# FPGA_Power.net
KiCad netlist of a schematic drawn in Altium Designer
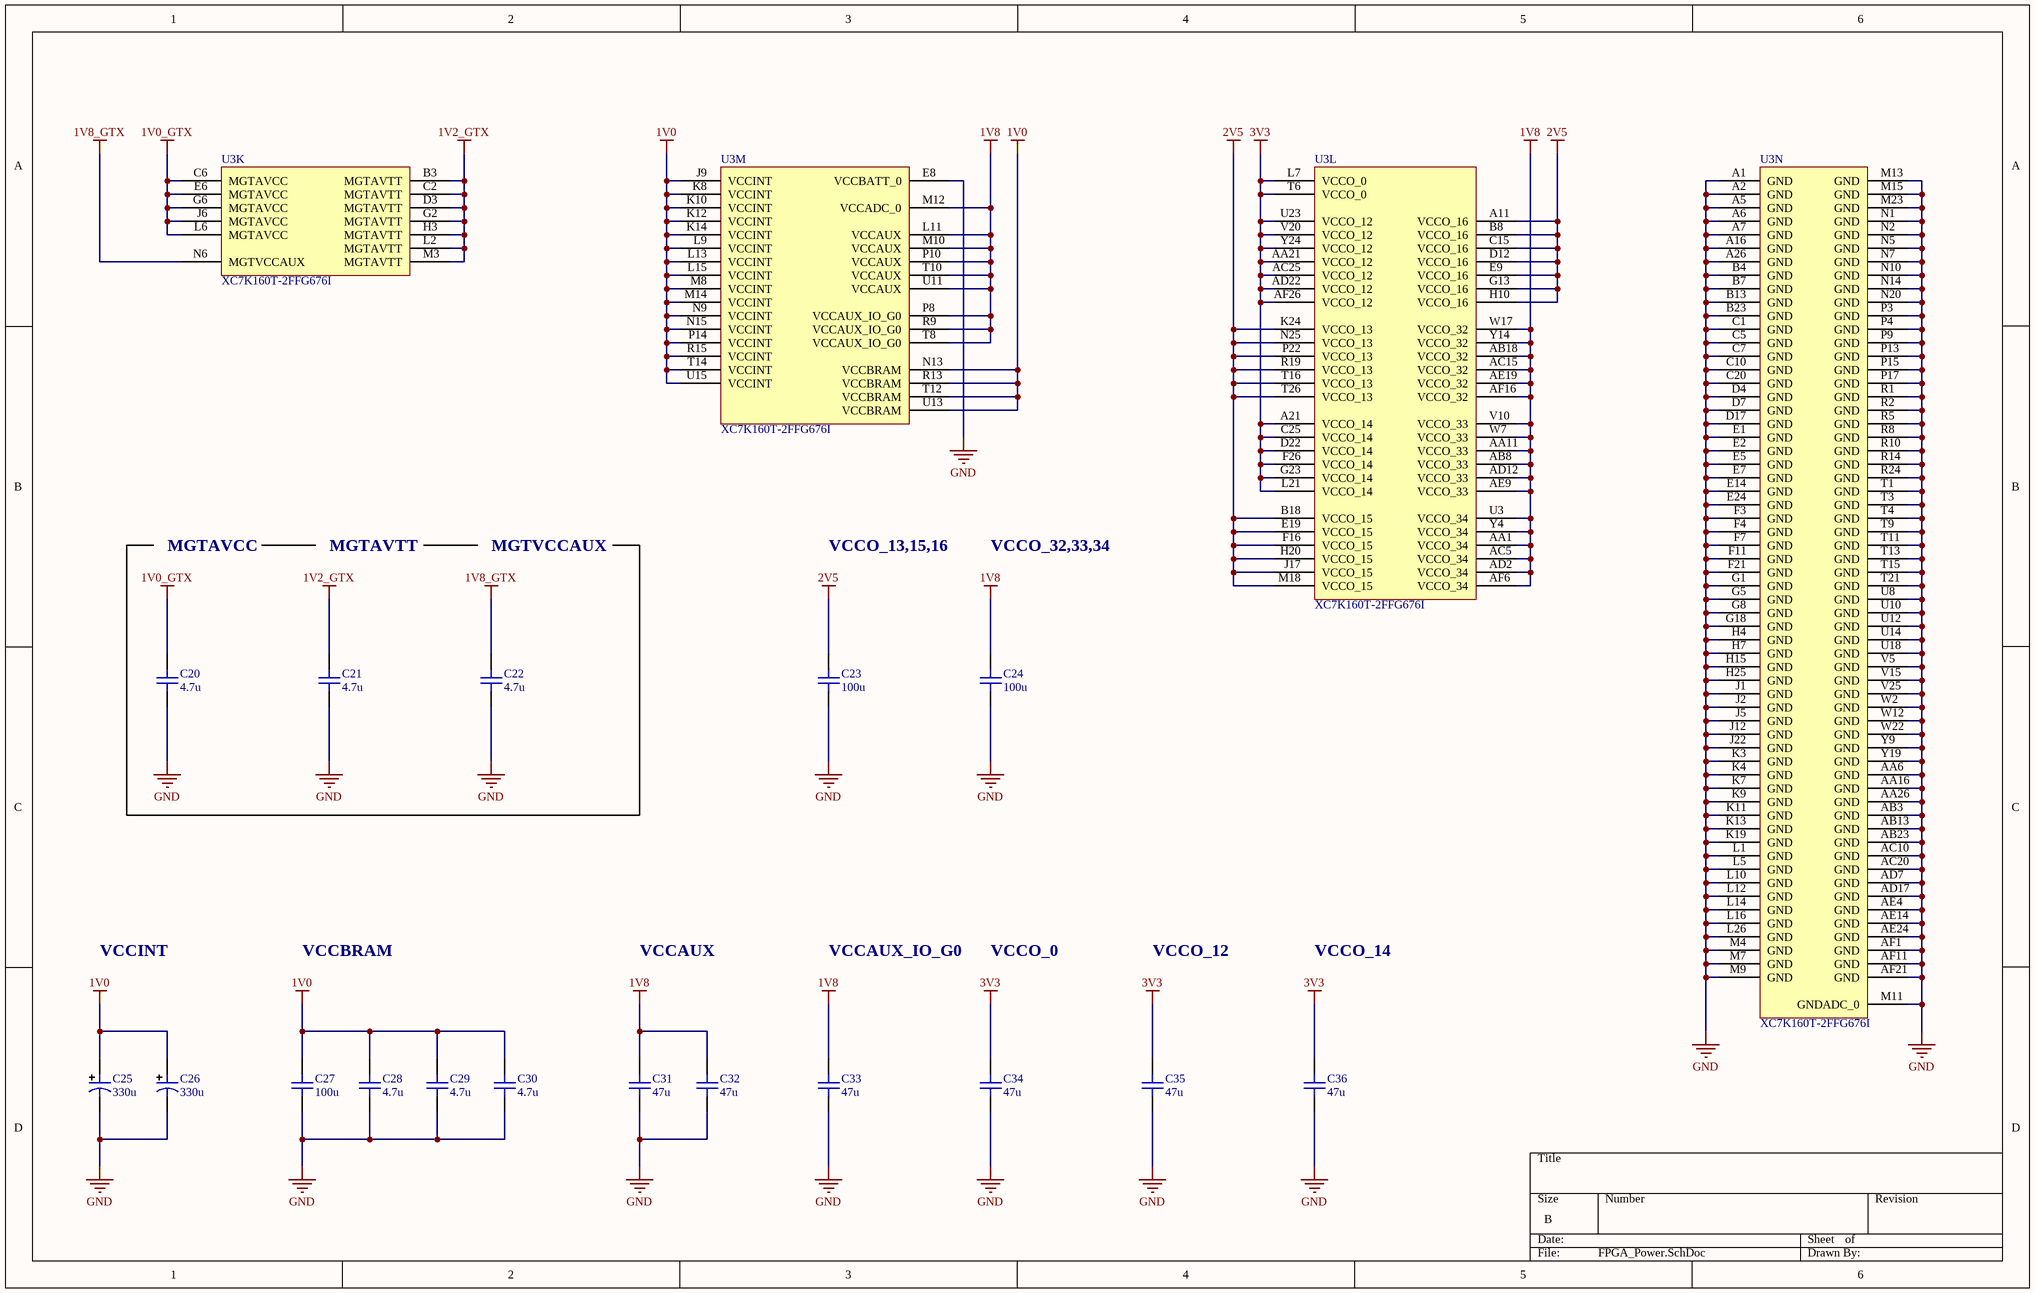
[diagram p0: FPGA_Power.SchDoc]

(export (version "E")
  (design (tool "Eeschema 10.0.6"))
  (components
    (comp (ref "C20")
      (value "4.7u")
      (footprint "C_0402_Generic")
      (description "4.7µF 10V X5R SMD ceramic capacitor in 0402 size")
      (fields
        (field (name "MANUFACTURER") "Murata Electronics")
        (field (name "MANUFACTURER PART NUMBER") "GRM155R61A475MEAAJ")
      )
      (libsource (lib "Capstone_Schematic_Library") (part "GRM155R61A475MEAAJ"))
    )
    (comp (ref "C21")
      (value "4.7u")
      (footprint "C_0402_Generic")
      (description "4.7µF 10V X5R SMD ceramic capacitor in 0402 size")
      (fields
        (field (name "MANUFACTURER") "Murata Electronics")
        (field (name "MANUFACTURER PART NUMBER") "GRM155R61A475MEAAJ")
      )
      (libsource (lib "Capstone_Schematic_Library") (part "GRM155R61A475MEAAJ"))
    )
    (comp (ref "C22")
      (value "4.7u")
      (footprint "C_0402_Generic")
      (description "4.7µF 10V X5R SMD ceramic capacitor in 0402 size")
      (fields
        (field (name "MANUFACTURER") "Murata Electronics")
        (field (name "MANUFACTURER PART NUMBER") "GRM155R61A475MEAAJ")
      )
      (libsource (lib "Capstone_Schematic_Library") (part "GRM155R61A475MEAAJ"))
    )
    (comp (ref "C23")
      (value "100u")
      (footprint "C_0805_Generic")
      (description "100µF 6.3V X5R SMD ceramic capacitor in 0805 size")
      (fields
        (field (name "MANUFACTURER") "Murata Electronics")
        (field (name "MANUFACTURER PART NUMBER") "GRM21BR60J107ME15L")
      )
      (libsource (lib "Capstone_Schematic_Library") (part "GRM21BR60J107ME15L"))
    )
    (comp (ref "C24")
      (value "100u")
      (footprint "C_0805_Generic")
      (description "100µF 6.3V X5R SMD ceramic capacitor in 0805 size")
      (fields
        (field (name "MANUFACTURER") "Murata Electronics")
        (field (name "MANUFACTURER PART NUMBER") "GRM21BR60J107ME15L")
      )
      (libsource (lib "Capstone_Schematic_Library") (part "GRM21BR60J107ME15L"))
    )
    (comp (ref "C25")
      (value "330u")
      (footprint "C_TANT_EIA-3528-21_B")
      (description "330µF 2.5V 15mOhm SMD tantalum capacitor in EIA-3528-21size")
      (fields
        (field (name "MANUFACTURER") "KEMET")
        (field (name "MANUFACTURER PART NUMBER") "T520B337M2R5ATE015")
      )
      (libsource (lib "Capstone_Schematic_Library") (part "T520B337M2R5ATE015"))
    )
    (comp (ref "C26")
      (value "330u")
      (footprint "C_TANT_EIA-3528-21_B")
      (description "330µF 2.5V 15mOhm SMD tantalum capacitor in EIA-3528-21size")
      (fields
        (field (name "MANUFACTURER") "KEMET")
        (field (name "MANUFACTURER PART NUMBER") "T520B337M2R5ATE015")
      )
      (libsource (lib "Capstone_Schematic_Library") (part "T520B337M2R5ATE015"))
    )
    (comp (ref "C27")
      (value "100u")
      (footprint "C_0805_Generic")
      (description "100µF 6.3V X5R SMD ceramic capacitor in 0805 size")
      (fields
        (field (name "MANUFACTURER") "Murata Electronics")
        (field (name "MANUFACTURER PART NUMBER") "GRM21BR60J107ME15L")
      )
      (libsource (lib "Capstone_Schematic_Library") (part "GRM21BR60J107ME15L"))
    )
    (comp (ref "C28")
      (value "4.7u")
      (footprint "C_0402_Generic")
      (description "4.7µF 10V X5R SMD ceramic capacitor in 0402 size")
      (fields
        (field (name "MANUFACTURER") "Murata Electronics")
        (field (name "MANUFACTURER PART NUMBER") "GRM155R61A475MEAAJ")
      )
      (libsource (lib "Capstone_Schematic_Library") (part "GRM155R61A475MEAAJ"))
    )
    (comp (ref "C29")
      (value "4.7u")
      (footprint "C_0402_Generic")
      (description "4.7µF 10V X5R SMD ceramic capacitor in 0402 size")
      (fields
        (field (name "MANUFACTURER") "Murata Electronics")
        (field (name "MANUFACTURER PART NUMBER") "GRM155R61A475MEAAJ")
      )
      (libsource (lib "Capstone_Schematic_Library") (part "GRM155R61A475MEAAJ"))
    )
    (comp (ref "C30")
      (value "4.7u")
      (footprint "C_0402_Generic")
      (description "4.7µF 10V X5R SMD ceramic capacitor in 0402 size")
      (fields
        (field (name "MANUFACTURER") "Murata Electronics")
        (field (name "MANUFACTURER PART NUMBER") "GRM155R61A475MEAAJ")
      )
      (libsource (lib "Capstone_Schematic_Library") (part "GRM155R61A475MEAAJ"))
    )
    (comp (ref "C31")
      (value "47u")
      (footprint "C_0603_Generic")
      (description "47µF 6.3V X5R SMD ceramic capacitor in 0603 size")
      (fields
        (field (name "MANUFACTURER") "Murata Electronics")
        (field (name "MANUFACTURER PART NUMBER") "GRM188R60J476ME15D")
      )
      (libsource (lib "Capstone_Schematic_Library") (part "GRM188R60J476ME15D"))
    )
    (comp (ref "C32")
      (value "47u")
      (footprint "C_0603_Generic")
      (description "47µF 6.3V X5R SMD ceramic capacitor in 0603 size")
      (fields
        (field (name "MANUFACTURER") "Murata Electronics")
        (field (name "MANUFACTURER PART NUMBER") "GRM188R60J476ME15D")
      )
      (libsource (lib "Capstone_Schematic_Library") (part "GRM188R60J476ME15D"))
    )
    (comp (ref "C33")
      (value "47u")
      (footprint "C_0603_Generic")
      (description "47µF 6.3V X5R SMD ceramic capacitor in 0603 size")
      (fields
        (field (name "MANUFACTURER") "Murata Electronics")
        (field (name "MANUFACTURER PART NUMBER") "GRM188R60J476ME15D")
      )
      (libsource (lib "Capstone_Schematic_Library") (part "GRM188R60J476ME15D"))
    )
    (comp (ref "C34")
      (value "47u")
      (footprint "C_0603_Generic")
      (description "47µF 6.3V X5R SMD ceramic capacitor in 0603 size")
      (fields
        (field (name "MANUFACTURER") "Murata Electronics")
        (field (name "MANUFACTURER PART NUMBER") "GRM188R60J476ME15D")
      )
      (libsource (lib "Capstone_Schematic_Library") (part "GRM188R60J476ME15D"))
    )
    (comp (ref "C35")
      (value "47u")
      (footprint "C_0603_Generic")
      (description "47µF 6.3V X5R SMD ceramic capacitor in 0603 size")
      (fields
        (field (name "MANUFACTURER") "Murata Electronics")
        (field (name "MANUFACTURER PART NUMBER") "GRM188R60J476ME15D")
      )
      (libsource (lib "Capstone_Schematic_Library") (part "GRM188R60J476ME15D"))
    )
    (comp (ref "C36")
      (value "47u")
      (footprint "C_0603_Generic")
      (description "47µF 6.3V X5R SMD ceramic capacitor in 0603 size")
      (fields
        (field (name "MANUFACTURER") "Murata Electronics")
        (field (name "MANUFACTURER PART NUMBER") "GRM188R60J476ME15D")
      )
      (libsource (lib "Capstone_Schematic_Library") (part "GRM188R60J476ME15D"))
    )
    (comp (ref "U3")
      (value "XC7K160T-2FFG676I")
      (footprint "FFG676_(XC7K160T-2FFG676I)")
      (description "Kintex-7 FPGA, 400 User I/Os, 8 GTX, 676-Ball BGA, Speed Grade 2, Industrial Grade, Pb-Free")
      (fields (field (name "MANUFACTURER") "AMD/Xilinx"))
      (libsource (lib "Capstone_Schematic_Library") (part "XC7K160T"))
    )
  )
  (nets
    (net (code "1") (name "1V0") (class "Default")
      (node (ref "C25") (pin "1") (pinfunction "1_1") (pintype "passive"))
      (node (ref "C26") (pin "1") (pinfunction "1_1") (pintype "passive"))
      (node (ref "C27") (pin "2") (pinfunction "2_2") (pintype "passive"))
      (node (ref "C28") (pin "2") (pinfunction "2_2") (pintype "passive"))
      (node (ref "C29") (pin "2") (pinfunction "2_2") (pintype "passive"))
      (node (ref "C30") (pin "2") (pinfunction "2_2") (pintype "passive"))
      (node (ref "U3") (pin "J9") (pinfunction "VCCINT_J9") (pintype "power_in"))
      (node (ref "U3") (pin "K10") (pinfunction "VCCINT_K10") (pintype "power_in"))
      (node (ref "U3") (pin "K12") (pinfunction "VCCINT_K12") (pintype "power_in"))
      (node (ref "U3") (pin "K14") (pinfunction "VCCINT_K14") (pintype "power_in"))
      (node (ref "U3") (pin "K8") (pinfunction "VCCINT_K8") (pintype "power_in"))
      (node (ref "U3") (pin "L13") (pinfunction "VCCINT_L13") (pintype "power_in"))
      (node (ref "U3") (pin "L15") (pinfunction "VCCINT_L15") (pintype "power_in"))
      (node (ref "U3") (pin "L9") (pinfunction "VCCINT_L9") (pintype "power_in"))
      (node (ref "U3") (pin "M14") (pinfunction "VCCINT_M14") (pintype "power_in"))
      (node (ref "U3") (pin "M8") (pinfunction "VCCINT_M8") (pintype "power_in"))
      (node (ref "U3") (pin "N13") (pinfunction "VCCBRAM_N13") (pintype "power_in"))
      (node (ref "U3") (pin "N15") (pinfunction "VCCINT_N15") (pintype "power_in"))
      (node (ref "U3") (pin "N9") (pinfunction "VCCINT_N9") (pintype "power_in"))
      (node (ref "U3") (pin "P14") (pinfunction "VCCINT_P14") (pintype "power_in"))
      (node (ref "U3") (pin "R13") (pinfunction "VCCBRAM_R13") (pintype "power_in"))
      (node (ref "U3") (pin "R15") (pinfunction "VCCINT_R15") (pintype "power_in"))
      (node (ref "U3") (pin "T12") (pinfunction "VCCBRAM_T12") (pintype "power_in"))
      (node (ref "U3") (pin "T14") (pinfunction "VCCINT_T14") (pintype "power_in"))
      (node (ref "U3") (pin "U13") (pinfunction "VCCBRAM_U13") (pintype "power_in"))
      (node (ref "U3") (pin "U15") (pinfunction "VCCINT_U15") (pintype "power_in"))
    )
    (net (code "2") (name "1V0_GTX") (class "Default")
      (node (ref "C20") (pin "2") (pinfunction "2_2") (pintype "passive"))
      (node (ref "U3") (pin "C6") (pinfunction "MGTAVCC_C6") (pintype "power_in"))
      (node (ref "U3") (pin "E6") (pinfunction "MGTAVCC_E6") (pintype "power_in"))
      (node (ref "U3") (pin "G6") (pinfunction "MGTAVCC_G6") (pintype "power_in"))
      (node (ref "U3") (pin "J6") (pinfunction "MGTAVCC_J6") (pintype "power_in"))
      (node (ref "U3") (pin "L6") (pinfunction "MGTAVCC_L6") (pintype "power_in"))
    )
    (net (code "3") (name "1V2_GTX") (class "Default")
      (node (ref "C21") (pin "2") (pinfunction "2_2") (pintype "passive"))
      (node (ref "U3") (pin "B3") (pinfunction "MGTAVTT_B3") (pintype "power_in"))
      (node (ref "U3") (pin "C2") (pinfunction "MGTAVTT_C2") (pintype "power_in"))
      (node (ref "U3") (pin "D3") (pinfunction "MGTAVTT_D3") (pintype "power_in"))
      (node (ref "U3") (pin "G2") (pinfunction "MGTAVTT_G2") (pintype "power_in"))
      (node (ref "U3") (pin "H3") (pinfunction "MGTAVTT_H3") (pintype "power_in"))
      (node (ref "U3") (pin "L2") (pinfunction "MGTAVTT_L2") (pintype "power_in"))
      (node (ref "U3") (pin "M3") (pinfunction "MGTAVTT_M3") (pintype "power_in"))
    )
    (net (code "4") (name "1V8") (class "Default")
      (node (ref "C24") (pin "2") (pinfunction "2_2") (pintype "passive"))
      (node (ref "C31") (pin "2") (pinfunction "2_2") (pintype "passive"))
      (node (ref "C32") (pin "2") (pinfunction "2_2") (pintype "passive"))
      (node (ref "C33") (pin "2") (pinfunction "2_2") (pintype "passive"))
      (node (ref "U3") (pin "AA1") (pinfunction "VCCO_34_AA1") (pintype "power_in"))
      (node (ref "U3") (pin "AA11") (pinfunction "VCCO_33_AA11") (pintype "power_in"))
      (node (ref "U3") (pin "AB18") (pinfunction "VCCO_32_AB18") (pintype "power_in"))
      (node (ref "U3") (pin "AB8") (pinfunction "VCCO_33_AB8") (pintype "power_in"))
      (node (ref "U3") (pin "AC15") (pinfunction "VCCO_32_AC15") (pintype "power_in"))
      (node (ref "U3") (pin "AC5") (pinfunction "VCCO_34_AC5") (pintype "power_in"))
      (node (ref "U3") (pin "AD12") (pinfunction "VCCO_33_AD12") (pintype "power_in"))
      (node (ref "U3") (pin "AD2") (pinfunction "VCCO_34_AD2") (pintype "power_in"))
      (node (ref "U3") (pin "AE19") (pinfunction "VCCO_32_AE19") (pintype "power_in"))
      (node (ref "U3") (pin "AE9") (pinfunction "VCCO_33_AE9") (pintype "power_in"))
      (node (ref "U3") (pin "AF16") (pinfunction "VCCO_32_AF16") (pintype "power_in"))
      (node (ref "U3") (pin "AF6") (pinfunction "VCCO_34_AF6") (pintype "power_in"))
      (node (ref "U3") (pin "L11") (pinfunction "VCCAUX_L11") (pintype "power_in"))
      (node (ref "U3") (pin "M10") (pinfunction "VCCAUX_M10") (pintype "power_in"))
      (node (ref "U3") (pin "M12") (pinfunction "VCCADC_0_M12") (pintype "power_in"))
      (node (ref "U3") (pin "P10") (pinfunction "VCCAUX_P10") (pintype "power_in"))
      (node (ref "U3") (pin "P8") (pinfunction "VCCAUX_IO_G0_P8") (pintype "power_in"))
      (node (ref "U3") (pin "R9") (pinfunction "VCCAUX_IO_G0_R9") (pintype "power_in"))
      (node (ref "U3") (pin "T10") (pinfunction "VCCAUX_T10") (pintype "power_in"))
      (node (ref "U3") (pin "T8") (pinfunction "VCCAUX_IO_G0_T8") (pintype "power_in"))
      (node (ref "U3") (pin "U11") (pinfunction "VCCAUX_U11") (pintype "power_in"))
      (node (ref "U3") (pin "U3") (pinfunction "VCCO_34_U3") (pintype "power_in"))
      (node (ref "U3") (pin "V10") (pinfunction "VCCO_33_V10") (pintype "power_in"))
      (node (ref "U3") (pin "W17") (pinfunction "VCCO_32_W17") (pintype "power_in"))
      (node (ref "U3") (pin "W7") (pinfunction "VCCO_33_W7") (pintype "power_in"))
      (node (ref "U3") (pin "Y14") (pinfunction "VCCO_32_Y14") (pintype "power_in"))
      (node (ref "U3") (pin "Y4") (pinfunction "VCCO_34_Y4") (pintype "power_in"))
    )
    (net (code "5") (name "1V8_GTX") (class "Default")
      (node (ref "C22") (pin "2") (pinfunction "2_2") (pintype "passive"))
      (node (ref "U3") (pin "N6") (pinfunction "MGTVCCAUX_N6") (pintype "power_in"))
    )
    (net (code "6") (name "2V5") (class "Default")
      (node (ref "C23") (pin "2") (pinfunction "2_2") (pintype "passive"))
      (node (ref "U3") (pin "A11") (pinfunction "VCCO_16_A11") (pintype "power_in"))
      (node (ref "U3") (pin "B18") (pinfunction "VCCO_15_B18") (pintype "power_in"))
      (node (ref "U3") (pin "B8") (pinfunction "VCCO_16_B8") (pintype "power_in"))
      (node (ref "U3") (pin "C15") (pinfunction "VCCO_16_C15") (pintype "power_in"))
      (node (ref "U3") (pin "D12") (pinfunction "VCCO_16_D12") (pintype "power_in"))
      (node (ref "U3") (pin "E19") (pinfunction "VCCO_15_E19") (pintype "power_in"))
      (node (ref "U3") (pin "E9") (pinfunction "VCCO_16_E9") (pintype "power_in"))
      (node (ref "U3") (pin "F16") (pinfunction "VCCO_15_F16") (pintype "power_in"))
      (node (ref "U3") (pin "G13") (pinfunction "VCCO_16_G13") (pintype "power_in"))
      (node (ref "U3") (pin "H10") (pinfunction "VCCO_16_H10") (pintype "power_in"))
      (node (ref "U3") (pin "H20") (pinfunction "VCCO_15_H20") (pintype "power_in"))
      (node (ref "U3") (pin "J17") (pinfunction "VCCO_15_J17") (pintype "power_in"))
      (node (ref "U3") (pin "K24") (pinfunction "VCCO_13_K24") (pintype "power_in"))
      (node (ref "U3") (pin "M18") (pinfunction "VCCO_15_M18") (pintype "power_in"))
      (node (ref "U3") (pin "N25") (pinfunction "VCCO_13_N25") (pintype "power_in"))
      (node (ref "U3") (pin "P22") (pinfunction "VCCO_13_P22") (pintype "power_in"))
      (node (ref "U3") (pin "R19") (pinfunction "VCCO_13_R19") (pintype "power_in"))
      (node (ref "U3") (pin "T16") (pinfunction "VCCO_13_T16") (pintype "power_in"))
      (node (ref "U3") (pin "T26") (pinfunction "VCCO_13_T26") (pintype "power_in"))
    )
    (net (code "7") (name "3V3") (class "Default")
      (node (ref "C34") (pin "2") (pinfunction "2_2") (pintype "passive"))
      (node (ref "C35") (pin "2") (pinfunction "2_2") (pintype "passive"))
      (node (ref "C36") (pin "2") (pinfunction "2_2") (pintype "passive"))
      (node (ref "U3") (pin "A21") (pinfunction "VCCO_14_A21") (pintype "power_in"))
      (node (ref "U3") (pin "AA21") (pinfunction "VCCO_12_AA21") (pintype "power_in"))
      (node (ref "U3") (pin "AC25") (pinfunction "VCCO_12_AC25") (pintype "power_in"))
      (node (ref "U3") (pin "AD22") (pinfunction "VCCO_12_AD22") (pintype "power_in"))
      (node (ref "U3") (pin "AF26") (pinfunction "VCCO_12_AF26") (pintype "power_in"))
      (node (ref "U3") (pin "C25") (pinfunction "VCCO_14_C25") (pintype "power_in"))
      (node (ref "U3") (pin "D22") (pinfunction "VCCO_14_D22") (pintype "power_in"))
      (node (ref "U3") (pin "F26") (pinfunction "VCCO_14_F26") (pintype "power_in"))
      (node (ref "U3") (pin "G23") (pinfunction "VCCO_14_G23") (pintype "power_in"))
      (node (ref "U3") (pin "L21") (pinfunction "VCCO_14_L21") (pintype "power_in"))
      (node (ref "U3") (pin "L7") (pinfunction "VCCO_0_L7") (pintype "power_in"))
      (node (ref "U3") (pin "T6") (pinfunction "VCCO_0_T6") (pintype "power_in"))
      (node (ref "U3") (pin "U23") (pinfunction "VCCO_12_U23") (pintype "power_in"))
      (node (ref "U3") (pin "V20") (pinfunction "VCCO_12_V20") (pintype "power_in"))
      (node (ref "U3") (pin "Y24") (pinfunction "VCCO_12_Y24") (pintype "power_in"))
    )
    (net (code "8") (name "GND") (class "Default")
      (node (ref "C20") (pin "1") (pinfunction "1_1") (pintype "passive"))
      (node (ref "C21") (pin "1") (pinfunction "1_1") (pintype "passive"))
      (node (ref "C22") (pin "1") (pinfunction "1_1") (pintype "passive"))
      (node (ref "C23") (pin "1") (pinfunction "1_1") (pintype "passive"))
      (node (ref "C24") (pin "1") (pinfunction "1_1") (pintype "passive"))
      (node (ref "C25") (pin "2") (pinfunction "2_2") (pintype "passive"))
      (node (ref "C26") (pin "2") (pinfunction "2_2") (pintype "passive"))
      (node (ref "C27") (pin "1") (pinfunction "1_1") (pintype "passive"))
      (node (ref "C28") (pin "1") (pinfunction "1_1") (pintype "passive"))
      (node (ref "C29") (pin "1") (pinfunction "1_1") (pintype "passive"))
      (node (ref "C30") (pin "1") (pinfunction "1_1") (pintype "passive"))
      (node (ref "C31") (pin "1") (pinfunction "1_1") (pintype "passive"))
      (node (ref "C32") (pin "1") (pinfunction "1_1") (pintype "passive"))
      (node (ref "C33") (pin "1") (pinfunction "1_1") (pintype "passive"))
      (node (ref "C34") (pin "1") (pinfunction "1_1") (pintype "passive"))
      (node (ref "C35") (pin "1") (pinfunction "1_1") (pintype "passive"))
      (node (ref "C36") (pin "1") (pinfunction "1_1") (pintype "passive"))
      (node (ref "U3") (pin "A1") (pinfunction "GND_A1") (pintype "power_in"))
      (node (ref "U3") (pin "A16") (pinfunction "GND_A16") (pintype "power_in"))
      (node (ref "U3") (pin "A2") (pinfunction "GND_A2") (pintype "power_in"))
      (node (ref "U3") (pin "A26") (pinfunction "GND_A26") (pintype "power_in"))
      (node (ref "U3") (pin "A5") (pinfunction "GND_A5") (pintype "power_in"))
      (node (ref "U3") (pin "A6") (pinfunction "GND_A6") (pintype "power_in"))
      (node (ref "U3") (pin "A7") (pinfunction "GND_A7") (pintype "power_in"))
      (node (ref "U3") (pin "AA16") (pinfunction "GND_AA16") (pintype "power_in"))
      (node (ref "U3") (pin "AA26") (pinfunction "GND_AA26") (pintype "power_in"))
      (node (ref "U3") (pin "AA6") (pinfunction "GND_AA6") (pintype "power_in"))
      (node (ref "U3") (pin "AB13") (pinfunction "GND_AB13") (pintype "power_in"))
      (node (ref "U3") (pin "AB23") (pinfunction "GND_AB23") (pintype "power_in"))
      (node (ref "U3") (pin "AB3") (pinfunction "GND_AB3") (pintype "power_in"))
      (node (ref "U3") (pin "AC10") (pinfunction "GND_AC10") (pintype "power_in"))
      (node (ref "U3") (pin "AC20") (pinfunction "GND_AC20") (pintype "power_in"))
      (node (ref "U3") (pin "AD17") (pinfunction "GND_AD17") (pintype "power_in"))
      (node (ref "U3") (pin "AD7") (pinfunction "GND_AD7") (pintype "power_in"))
      (node (ref "U3") (pin "AE14") (pinfunction "GND_AE14") (pintype "power_in"))
      (node (ref "U3") (pin "AE24") (pinfunction "GND_AE24") (pintype "power_in"))
      (node (ref "U3") (pin "AE4") (pinfunction "GND_AE4") (pintype "power_in"))
      (node (ref "U3") (pin "AF1") (pinfunction "GND_AF1") (pintype "power_in"))
      (node (ref "U3") (pin "AF11") (pinfunction "GND_AF11") (pintype "power_in"))
      (node (ref "U3") (pin "AF21") (pinfunction "GND_AF21") (pintype "power_in"))
      (node (ref "U3") (pin "B13") (pinfunction "GND_B13") (pintype "power_in"))
      (node (ref "U3") (pin "B23") (pinfunction "GND_B23") (pintype "power_in"))
      (node (ref "U3") (pin "B4") (pinfunction "GND_B4") (pintype "power_in"))
      (node (ref "U3") (pin "B7") (pinfunction "GND_B7") (pintype "power_in"))
      (node (ref "U3") (pin "C1") (pinfunction "GND_C1") (pintype "power_in"))
      (node (ref "U3") (pin "C10") (pinfunction "GND_C10") (pintype "power_in"))
      (node (ref "U3") (pin "C20") (pinfunction "GND_C20") (pintype "power_in"))
      (node (ref "U3") (pin "C5") (pinfunction "GND_C5") (pintype "power_in"))
      (node (ref "U3") (pin "C7") (pinfunction "GND_C7") (pintype "power_in"))
      (node (ref "U3") (pin "D17") (pinfunction "GND_D17") (pintype "power_in"))
      (node (ref "U3") (pin "D4") (pinfunction "GND_D4") (pintype "power_in"))
      (node (ref "U3") (pin "D7") (pinfunction "GND_D7") (pintype "power_in"))
      (node (ref "U3") (pin "E1") (pinfunction "GND_E1") (pintype "power_in"))
      (node (ref "U3") (pin "E14") (pinfunction "GND_E14") (pintype "power_in"))
      (node (ref "U3") (pin "E2") (pinfunction "GND_E2") (pintype "power_in"))
      (node (ref "U3") (pin "E24") (pinfunction "GND_E24") (pintype "power_in"))
      (node (ref "U3") (pin "E5") (pinfunction "GND_E5") (pintype "power_in"))
      (node (ref "U3") (pin "E7") (pinfunction "GND_E7") (pintype "power_in"))
      (node (ref "U3") (pin "E8") (pinfunction "VCCBATT_0_E8") (pintype "power_in"))
      (node (ref "U3") (pin "F11") (pinfunction "GND_F11") (pintype "power_in"))
      (node (ref "U3") (pin "F21") (pinfunction "GND_F21") (pintype "power_in"))
      (node (ref "U3") (pin "F3") (pinfunction "GND_F3") (pintype "power_in"))
      (node (ref "U3") (pin "F4") (pinfunction "GND_F4") (pintype "power_in"))
      (node (ref "U3") (pin "F7") (pinfunction "GND_F7") (pintype "power_in"))
      (node (ref "U3") (pin "G1") (pinfunction "GND_G1") (pintype "power_in"))
      (node (ref "U3") (pin "G18") (pinfunction "GND_G18") (pintype "power_in"))
      (node (ref "U3") (pin "G5") (pinfunction "GND_G5") (pintype "power_in"))
      (node (ref "U3") (pin "G8") (pinfunction "GND_G8") (pintype "power_in"))
      (node (ref "U3") (pin "H15") (pinfunction "GND_H15") (pintype "power_in"))
      (node (ref "U3") (pin "H25") (pinfunction "GND_H25") (pintype "power_in"))
      (node (ref "U3") (pin "H4") (pinfunction "GND_H4") (pintype "power_in"))
      (node (ref "U3") (pin "H7") (pinfunction "GND_H7") (pintype "power_in"))
      (node (ref "U3") (pin "J1") (pinfunction "GND_J1") (pintype "power_in"))
      (node (ref "U3") (pin "J12") (pinfunction "GND_J12") (pintype "power_in"))
      (node (ref "U3") (pin "J2") (pinfunction "GND_J2") (pintype "power_in"))
      (node (ref "U3") (pin "J22") (pinfunction "GND_J22") (pintype "power_in"))
      (node (ref "U3") (pin "J5") (pinfunction "GND_J5") (pintype "power_in"))
      (node (ref "U3") (pin "K11") (pinfunction "GND_K11") (pintype "power_in"))
      (node (ref "U3") (pin "K13") (pinfunction "GND_K13") (pintype "power_in"))
      (node (ref "U3") (pin "K19") (pinfunction "GND_K19") (pintype "power_in"))
      (node (ref "U3") (pin "K3") (pinfunction "GND_K3") (pintype "power_in"))
      (node (ref "U3") (pin "K4") (pinfunction "GND_K4") (pintype "power_in"))
      (node (ref "U3") (pin "K7") (pinfunction "GND_K7") (pintype "power_in"))
      (node (ref "U3") (pin "K9") (pinfunction "GND_K9") (pintype "power_in"))
      (node (ref "U3") (pin "L1") (pinfunction "GND_L1") (pintype "power_in"))
      (node (ref "U3") (pin "L10") (pinfunction "GND_L10") (pintype "power_in"))
      (node (ref "U3") (pin "L12") (pinfunction "GND_L12") (pintype "power_in"))
      (node (ref "U3") (pin "L14") (pinfunction "GND_L14") (pintype "power_in"))
      (node (ref "U3") (pin "L16") (pinfunction "GND_L16") (pintype "power_in"))
      (node (ref "U3") (pin "L26") (pinfunction "GND_L26") (pintype "power_in"))
      (node (ref "U3") (pin "L5") (pinfunction "GND_L5") (pintype "power_in"))
      (node (ref "U3") (pin "M11") (pinfunction "GNDADC_0_M11") (pintype "power_in"))
      (node (ref "U3") (pin "M13") (pinfunction "GND_M13") (pintype "power_in"))
      (node (ref "U3") (pin "M15") (pinfunction "GND_M15") (pintype "power_in"))
      (node (ref "U3") (pin "M23") (pinfunction "GND_M23") (pintype "power_in"))
      (node (ref "U3") (pin "M4") (pinfunction "GND_M4") (pintype "power_in"))
      (node (ref "U3") (pin "M7") (pinfunction "GND_M7") (pintype "power_in"))
      (node (ref "U3") (pin "M9") (pinfunction "GND_M9") (pintype "power_in"))
      (node (ref "U3") (pin "N1") (pinfunction "GND_N1") (pintype "power_in"))
      (node (ref "U3") (pin "N10") (pinfunction "GND_N10") (pintype "power_in"))
      (node (ref "U3") (pin "N14") (pinfunction "GND_N14") (pintype "power_in"))
      (node (ref "U3") (pin "N2") (pinfunction "GND_N2") (pintype "power_in"))
      (node (ref "U3") (pin "N20") (pinfunction "GND_N20") (pintype "power_in"))
      (node (ref "U3") (pin "N5") (pinfunction "GND_N5") (pintype "power_in"))
      (node (ref "U3") (pin "N7") (pinfunction "GND_N7") (pintype "power_in"))
      (node (ref "U3") (pin "P13") (pinfunction "GND_P13") (pintype "power_in"))
      (node (ref "U3") (pin "P15") (pinfunction "GND_P15") (pintype "power_in"))
      (node (ref "U3") (pin "P17") (pinfunction "GND_P17") (pintype "power_in"))
      (node (ref "U3") (pin "P3") (pinfunction "GND_P3") (pintype "power_in"))
      (node (ref "U3") (pin "P4") (pinfunction "GND_P4") (pintype "power_in"))
      (node (ref "U3") (pin "P9") (pinfunction "GND_P9") (pintype "power_in"))
      (node (ref "U3") (pin "R1") (pinfunction "GND_R1") (pintype "power_in"))
      (node (ref "U3") (pin "R10") (pinfunction "GND_R10") (pintype "power_in"))
      (node (ref "U3") (pin "R14") (pinfunction "GND_R14") (pintype "power_in"))
      (node (ref "U3") (pin "R2") (pinfunction "GND_R2") (pintype "power_in"))
      (node (ref "U3") (pin "R24") (pinfunction "GND_R24") (pintype "power_in"))
      (node (ref "U3") (pin "R5") (pinfunction "GND_R5") (pintype "power_in"))
      (node (ref "U3") (pin "R8") (pinfunction "GND_R8") (pintype "power_in"))
      (node (ref "U3") (pin "T1") (pinfunction "GND_T1") (pintype "power_in"))
      (node (ref "U3") (pin "T11") (pinfunction "GND_T11") (pintype "power_in"))
      (node (ref "U3") (pin "T13") (pinfunction "GND_T13") (pintype "power_in"))
      (node (ref "U3") (pin "T15") (pinfunction "GND_T15") (pintype "power_in"))
      (node (ref "U3") (pin "T21") (pinfunction "GND_T21") (pintype "power_in"))
      (node (ref "U3") (pin "T3") (pinfunction "GND_T3") (pintype "power_in"))
      (node (ref "U3") (pin "T4") (pinfunction "GND_T4") (pintype "power_in"))
      (node (ref "U3") (pin "T9") (pinfunction "GND_T9") (pintype "power_in"))
      (node (ref "U3") (pin "U10") (pinfunction "GND_U10") (pintype "power_in"))
      (node (ref "U3") (pin "U12") (pinfunction "GND_U12") (pintype "power_in"))
      (node (ref "U3") (pin "U14") (pinfunction "GND_U14") (pintype "power_in"))
      (node (ref "U3") (pin "U18") (pinfunction "GND_U18") (pintype "power_in"))
      (node (ref "U3") (pin "U8") (pinfunction "GND_U8") (pintype "power_in"))
      (node (ref "U3") (pin "V15") (pinfunction "GND_V15") (pintype "power_in"))
      (node (ref "U3") (pin "V25") (pinfunction "GND_V25") (pintype "power_in"))
      (node (ref "U3") (pin "V5") (pinfunction "GND_V5") (pintype "power_in"))
      (node (ref "U3") (pin "W12") (pinfunction "GND_W12") (pintype "power_in"))
      (node (ref "U3") (pin "W2") (pinfunction "GND_W2") (pintype "power_in"))
      (node (ref "U3") (pin "W22") (pinfunction "GND_W22") (pintype "power_in"))
      (node (ref "U3") (pin "Y19") (pinfunction "GND_Y19") (pintype "power_in"))
      (node (ref "U3") (pin "Y9") (pinfunction "GND_Y9") (pintype "power_in"))
    )
  )
)
